# Nodemcu_Door_Sensor.net
KiCad netlist of a schematic drawn in EAGLE
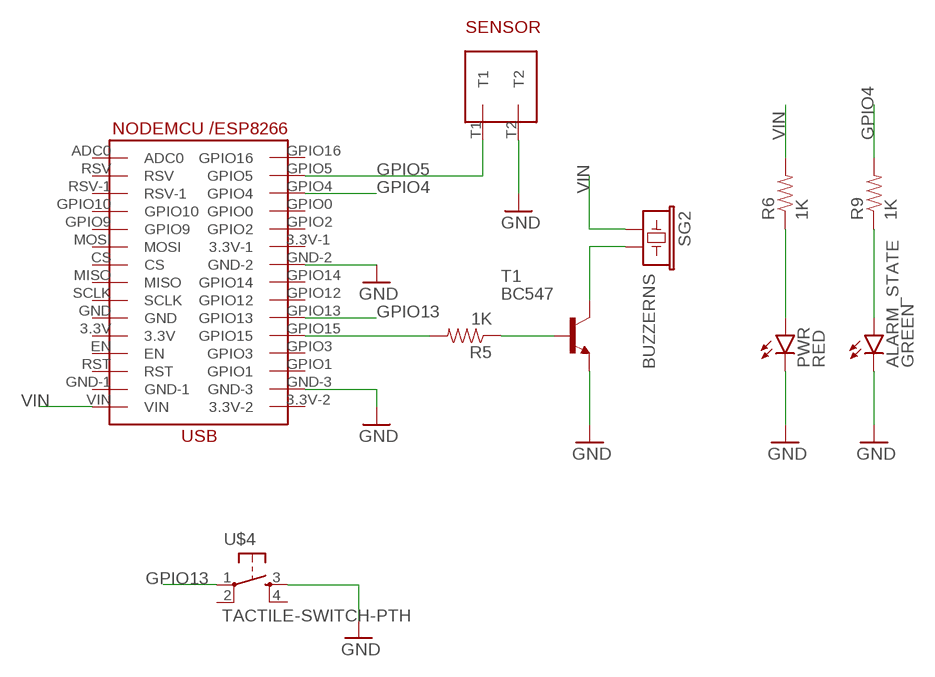
[diagram p0: schematic, sheet 1]

(export (version "E")
  (design (tool "Eeschema 10.0.6"))
  (components
    (comp (ref "ALARM_STATE")
      (value "GREEN")
      (footprint "eagle-import:LED3MM")
      (libsource (lib "eagle-import") (part "LED3MM"))
    )
    (comp (ref "PWR")
      (value "RED")
      (footprint "eagle-import:LED3MM")
      (libsource (lib "eagle-import") (part "LED3MM"))
    )
    (comp (ref "R5")
      (value "1K")
      (footprint "eagle-import:AXIAL-0.4")
      (libsource (lib "eagle-import") (part "RESISTORPTH-1/4W"))
    )
    (comp (ref "R6")
      (value "1K")
      (footprint "eagle-import:AXIAL-0.4")
      (libsource (lib "eagle-import") (part "RESISTORPTH-1/4W"))
    )
    (comp (ref "R9")
      (value "1K")
      (footprint "eagle-import:AXIAL-0.4")
      (libsource (lib "eagle-import") (part "RESISTORPTH-1/4W"))
    )
    (comp (ref "SENSOR")
      (value "TER_CON_2PIN_ROINCOPTH")
      (footprint "eagle-import:TER_CON_2PIN_ROINCO")
      (libsource (lib "eagle-import") (part "TER_CON_2PIN_ROINCOPTH"))
    )
    (comp (ref "SG2")
      (value "BUZZERNS")
      (footprint "eagle-import:BUZZER-12MM-NS")
      (libsource (lib "eagle-import") (part "BUZZERNS"))
    )
    (comp (ref "T1")
      (value "BC547")
      (footprint "eagle-import:TO92")
      (libsource (lib "eagle-import") (part "BC547"))
    )
    (comp (ref "U$1")
      (value "ROINCO_NODEMCU_ESP8266")
      (footprint "eagle-import:ROINCO_NODEMCU_ESP8266")
      (libsource (lib "eagle-import") (part "ROINCO_NODEMCU_ESP8266"))
    )
    (comp (ref "U$4")
      (value "TACTILE-SWITCH-PTH")
      (footprint "eagle-import:TAC-SWITCH-PTH")
      (libsource (lib "eagle-import") (part "TACTILE-SWITCH-PTH"))
    )
  )
  (nets
    (net (code "1") (name "/GPIO4") (class "Default")
      (node (ref "R9") (pin "P$2") (pinfunction "2_P$2") (pintype "passive"))
      (node (ref "U$1") (pin "GPIO4") (pinfunction "GPIO4_GPIO4") (pintype "bidirectional"))
    )
    (net (code "2") (name "/GPIO5") (class "Default")
      (node (ref "SENSOR") (pin "T1") (pinfunction "T1_T1") (pintype "bidirectional"))
      (node (ref "U$1") (pin "GPIO5") (pinfunction "GPIO5_GPIO5") (pintype "bidirectional"))
    )
    (net (code "3") (name "/GPIO13") (class "Default")
      (node (ref "U$1") (pin "GPIO13") (pinfunction "GPIO13_GPIO13") (pintype "bidirectional"))
      (node (ref "U$4") (pin "1") (pinfunction "1_1") (pintype "passive"))
    )
    (net (code "4") (name "/VIN") (class "Default")
      (node (ref "R6") (pin "P$2") (pinfunction "2_P$2") (pintype "passive"))
      (node (ref "SG2") (pin "+") (pinfunction "1_+") (pintype "passive"))
      (node (ref "U$1") (pin "VIN") (pinfunction "VIN_VIN") (pintype "bidirectional"))
    )
    (net (code "5") (name "GND") (class "Default")
      (node (ref "ALARM_STATE") (pin "K") (pinfunction "C_K") (pintype "passive"))
      (node (ref "PWR") (pin "K") (pinfunction "C_K") (pintype "passive"))
      (node (ref "SENSOR") (pin "T2") (pinfunction "T2_T2") (pintype "bidirectional"))
      (node (ref "T1") (pin "1") (pinfunction "E_1") (pintype "passive"))
      (node (ref "U$1") (pin "GND-2") (pinfunction "GND-2_GND-2") (pintype "bidirectional"))
      (node (ref "U$1") (pin "GND-3") (pinfunction "GND-3_GND-3") (pintype "bidirectional"))
      (node (ref "U$4") (pin "3") (pinfunction "3_3") (pintype "passive"))
    )
    (net (code "6") (name "Net-(R5-1)") (class "Default")
      (node (ref "R5") (pin "P$1") (pinfunction "1_P$1") (pintype "passive"))
      (node (ref "T1") (pin "2") (pinfunction "B_2") (pintype "passive"))
    )
    (net (code "7") (name "Net-(R5-2)") (class "Default")
      (node (ref "R5") (pin "P$2") (pinfunction "2_P$2") (pintype "passive"))
      (node (ref "U$1") (pin "GPIO15") (pinfunction "GPIO15_GPIO15") (pintype "bidirectional"))
    )
    (net (code "8") (name "Net-(R6-1)") (class "Default")
      (node (ref "PWR") (pin "A") (pinfunction "A_A") (pintype "passive"))
      (node (ref "R6") (pin "P$1") (pinfunction "1_P$1") (pintype "passive"))
    )
    (net (code "9") (name "Net-(R9-1)") (class "Default")
      (node (ref "ALARM_STATE") (pin "A") (pinfunction "A_A") (pintype "passive"))
      (node (ref "R9") (pin "P$1") (pinfunction "1_P$1") (pintype "passive"))
    )
    (net (code "10") (name "Net-(SG2-2)") (class "Default")
      (node (ref "SG2") (pin "-") (pinfunction "2_-") (pintype "passive"))
      (node (ref "T1") (pin "3") (pinfunction "C_3") (pintype "passive"))
    )
    (net (code "11") (name "unconnected-(U$1-Pad3.3V)") (class "Default")
      (node (ref "U$1") (pin "3.3V") (pinfunction "3.3V_3.3V") (pintype "bidirectional"))
    )
    (net (code "12") (name "unconnected-(U$1-Pad3.3V-1)") (class "Default")
      (node (ref "U$1") (pin "3.3V-1") (pinfunction "3.3V-1_3.3V-1") (pintype "bidirectional"))
    )
    (net (code "13") (name "unconnected-(U$1-Pad3.3V-2)") (class "Default")
      (node (ref "U$1") (pin "3.3V-2") (pinfunction "3.3V-2_3.3V-2") (pintype "bidirectional"))
    )
    (net (code "14") (name "unconnected-(U$1-PadADC0)") (class "Default")
      (node (ref "U$1") (pin "ADC0") (pinfunction "ADC0_ADC0") (pintype "bidirectional"))
    )
    (net (code "15") (name "unconnected-(U$1-PadCS)") (class "Default")
      (node (ref "U$1") (pin "CS") (pinfunction "CS_CS") (pintype "bidirectional"))
    )
    (net (code "16") (name "unconnected-(U$1-PadEN)") (class "Default")
      (node (ref "U$1") (pin "EN") (pinfunction "EN_EN") (pintype "bidirectional"))
    )
    (net (code "17") (name "unconnected-(U$1-PadGND)") (class "Default")
      (node (ref "U$1") (pin "GND") (pinfunction "GND_GND") (pintype "bidirectional"))
    )
    (net (code "18") (name "unconnected-(U$1-PadGND-1)") (class "Default")
      (node (ref "U$1") (pin "GND-1") (pinfunction "GND-1_GND-1") (pintype "bidirectional"))
    )
    (net (code "19") (name "unconnected-(U$1-PadGPIO0)") (class "Default")
      (node (ref "U$1") (pin "GPIO0") (pinfunction "GPIO0_GPIO0") (pintype "bidirectional"))
    )
    (net (code "20") (name "unconnected-(U$1-PadGPIO1)") (class "Default")
      (node (ref "U$1") (pin "GPIO1") (pinfunction "GPIO1_GPIO1") (pintype "bidirectional"))
    )
    (net (code "21") (name "unconnected-(U$1-PadGPIO2)") (class "Default")
      (node (ref "U$1") (pin "GPIO2") (pinfunction "GPIO2_GPIO2") (pintype "bidirectional"))
    )
    (net (code "22") (name "unconnected-(U$1-PadGPIO3)") (class "Default")
      (node (ref "U$1") (pin "GPIO3") (pinfunction "GPIO3_GPIO3") (pintype "bidirectional"))
    )
    (net (code "23") (name "unconnected-(U$1-PadGPIO9)") (class "Default")
      (node (ref "U$1") (pin "GPIO9") (pinfunction "GPIO9_GPIO9") (pintype "bidirectional"))
    )
    (net (code "24") (name "unconnected-(U$1-PadGPIO10)") (class "Default")
      (node (ref "U$1") (pin "GPIO10") (pinfunction "GPIO10_GPIO10") (pintype "bidirectional"))
    )
    (net (code "25") (name "unconnected-(U$1-PadGPIO12)") (class "Default")
      (node (ref "U$1") (pin "GPIO12") (pinfunction "GPIO12_GPIO12") (pintype "bidirectional"))
    )
    (net (code "26") (name "unconnected-(U$1-PadGPIO14)") (class "Default")
      (node (ref "U$1") (pin "GPIO14") (pinfunction "GPIO14_GPIO14") (pintype "bidirectional"))
    )
    (net (code "27") (name "unconnected-(U$1-PadGPIO16)") (class "Default")
      (node (ref "U$1") (pin "GPIO16") (pinfunction "GPIO16_GPIO16") (pintype "bidirectional"))
    )
    (net (code "28") (name "unconnected-(U$1-PadMISO)") (class "Default")
      (node (ref "U$1") (pin "MISO") (pinfunction "MISO_MISO") (pintype "bidirectional"))
    )
    (net (code "29") (name "unconnected-(U$1-PadMOSI)") (class "Default")
      (node (ref "U$1") (pin "MOSI") (pinfunction "MOSI_MOSI") (pintype "bidirectional"))
    )
    (net (code "30") (name "unconnected-(U$1-PadRST)") (class "Default")
      (node (ref "U$1") (pin "RST") (pinfunction "RST_RST") (pintype "bidirectional"))
    )
    (net (code "31") (name "unconnected-(U$1-PadRSV)") (class "Default")
      (node (ref "U$1") (pin "RSV") (pinfunction "RSV_RSV") (pintype "bidirectional"))
    )
    (net (code "32") (name "unconnected-(U$1-PadRSV-1)") (class "Default")
      (node (ref "U$1") (pin "RSV-1") (pinfunction "RSV-1_RSV-1") (pintype "bidirectional"))
    )
    (net (code "33") (name "unconnected-(U$1-PadSCLK)") (class "Default")
      (node (ref "U$1") (pin "SCLK") (pinfunction "SCLK_SCLK") (pintype "bidirectional"))
    )
    (net (code "34") (name "unconnected-(U$4-Pad2)") (class "Default")
      (node (ref "U$4") (pin "2") (pinfunction "2_2") (pintype "passive"))
    )
    (net (code "35") (name "unconnected-(U$4-Pad4)") (class "Default")
      (node (ref "U$4") (pin "4") (pinfunction "4_4") (pintype "passive"))
    )
  )
)
